# LCMeter_test_power_inverter.net
KiCad netlist of a schematic drawn in EAGLE
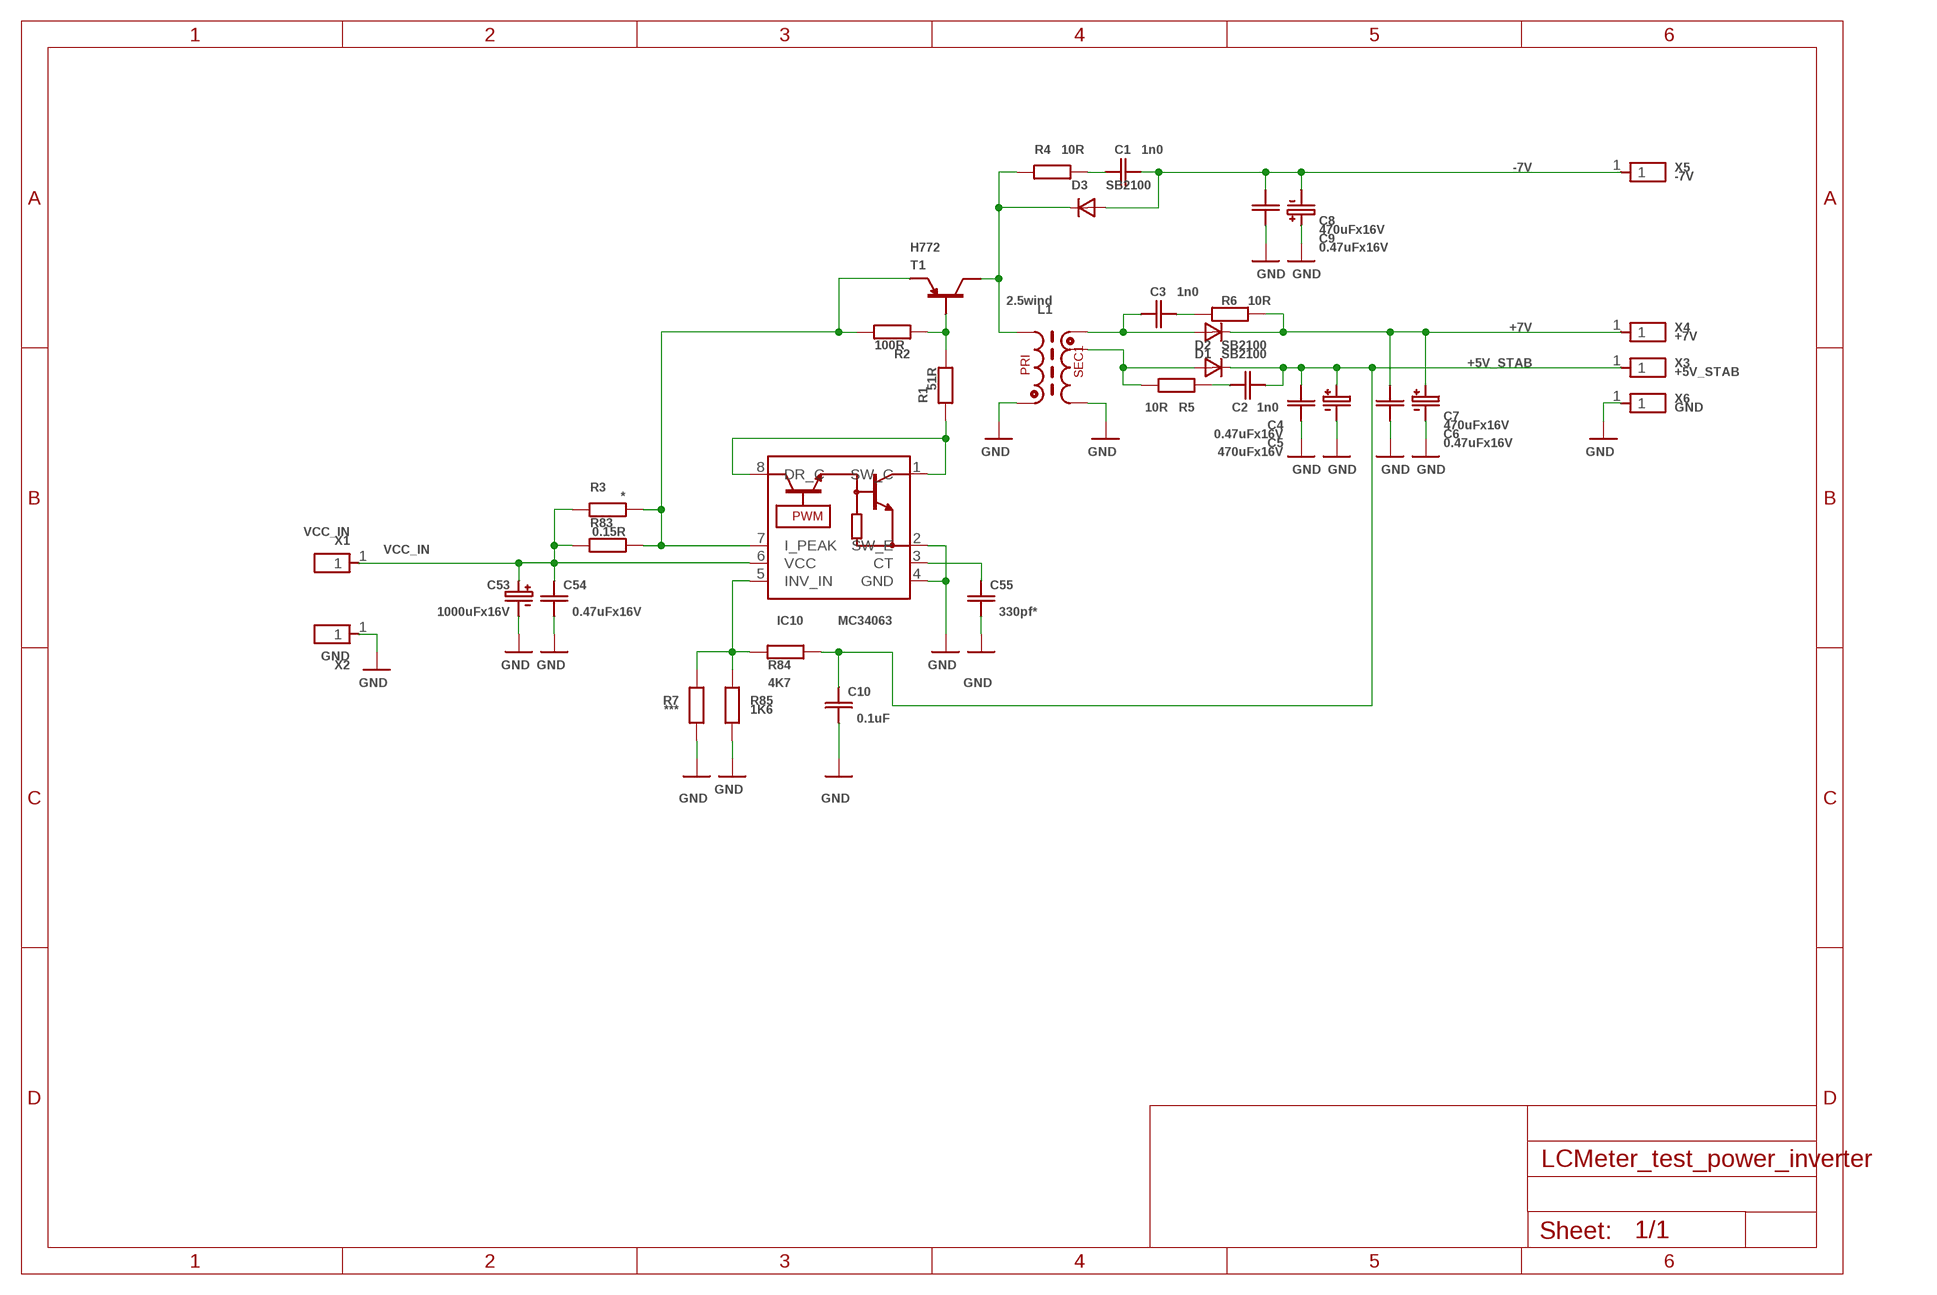
[diagram p0: schematic, sheet 1]

(export (version "E")
  (design (tool "Eeschema 10.0.6"))
  (components
    (comp (ref "C1")
      (value "1n0")
      (footprint "eagle-import:RSMD_0805")
      (libsource (lib "eagle-import") (part "CSMD_0805"))
    )
    (comp (ref "C2")
      (value "1n0")
      (footprint "eagle-import:RSMD_0805")
      (libsource (lib "eagle-import") (part "CSMD_0805"))
    )
    (comp (ref "C3")
      (value "1n0")
      (footprint "eagle-import:RSMD_0805")
      (libsource (lib "eagle-import") (part "CSMD_0805"))
    )
    (comp (ref "C4")
      (value "0.47uFx16V")
      (footprint "eagle-import:RSMD_1206_BIG_GAP")
      (libsource (lib "eagle-import") (part "CSMD_1206_BIG_GAP"))
    )
    (comp (ref "C5")
      (value "470uFx16V")
      (footprint "eagle-import:CE_10MM")
      (libsource (lib "eagle-import") (part "CE10MM"))
    )
    (comp (ref "C6")
      (value "0.47uFx16V")
      (footprint "eagle-import:RSMD_1206_BIG_GAP")
      (libsource (lib "eagle-import") (part "CSMD_1206_BIG_GAP"))
    )
    (comp (ref "C7")
      (value "470uFx16V")
      (footprint "eagle-import:CE_10MM")
      (libsource (lib "eagle-import") (part "CE10MM"))
    )
    (comp (ref "C8")
      (value "470uFx16V")
      (footprint "eagle-import:CE_10MM")
      (libsource (lib "eagle-import") (part "CE10MM"))
    )
    (comp (ref "C9")
      (value "0.47uFx16V")
      (footprint "eagle-import:RSMD_1206_BIG_GAP")
      (libsource (lib "eagle-import") (part "CSMD_1206_BIG_GAP"))
    )
    (comp (ref "C10")
      (value "0.1uF")
      (footprint "eagle-import:RSMD_0805")
      (libsource (lib "eagle-import") (part "CSMD_0805"))
    )
    (comp (ref "C53")
      (value "1000uFx16V")
      (footprint "eagle-import:CE_10MM")
      (libsource (lib "eagle-import") (part "CE10MM"))
    )
    (comp (ref "C54")
      (value "0.47uFx16V")
      (footprint "eagle-import:RSMD_1206")
      (libsource (lib "eagle-import") (part "CSMD_1206"))
    )
    (comp (ref "C55")
      (value "330pf*")
      (footprint "eagle-import:RSMD_0805")
      (libsource (lib "eagle-import") (part "CSMD_0805"))
    )
    (comp (ref "D1")
      (value "SB2100")
      (footprint "eagle-import:DO-41_12.5MM")
      (libsource (lib "eagle-import") (part "1N4001DO-41_12.5MM"))
    )
    (comp (ref "D2")
      (value "SB2100")
      (footprint "eagle-import:DO-41_5MM")
      (libsource (lib "eagle-import") (part "1N4001DO-41_5MM"))
    )
    (comp (ref "D3")
      (value "SB2100")
      (footprint "eagle-import:DO-41_12.5MM")
      (libsource (lib "eagle-import") (part "1N4001DO-41_12.5MM"))
    )
    (comp (ref "IC10")
      (value "MC34063")
      (footprint "eagle-import:SOIC8")
      (libsource (lib "eagle-import") (part "MC34063(SO-8)"))
    )
    (comp (ref "L1")
      (value "2.5wind")
      (footprint "eagle-import:RING_16X8_2.5WIND")
      (libsource (lib "eagle-import") (part "TRANS_2.5_WIND16X8"))
    )
    (comp (ref "R1")
      (value "51R")
      (footprint "eagle-import:RSMD_1206_BIG_GAP")
      (libsource (lib "eagle-import") (part "RSMD_1206_BIG_GAP"))
    )
    (comp (ref "R2")
      (value "100R")
      (footprint "eagle-import:RSMD_0805")
      (libsource (lib "eagle-import") (part "RSMD_0805"))
    )
    (comp (ref "R3")
      (value "*")
      (footprint "eagle-import:RSMD_1206_BIG_GAP")
      (libsource (lib "eagle-import") (part "RSMD_1206_BIG_GAP"))
    )
    (comp (ref "R4")
      (value "10R")
      (footprint "eagle-import:RSMD_1206_BIG_GAP")
      (libsource (lib "eagle-import") (part "RSMD_1206_BIG_GAP"))
    )
    (comp (ref "R5")
      (value "10R")
      (footprint "eagle-import:RSMD_1206_BIG_GAP")
      (libsource (lib "eagle-import") (part "RSMD_1206_BIG_GAP"))
    )
    (comp (ref "R6")
      (value "10R")
      (footprint "eagle-import:RSMD_1206_BIG_GAP")
      (libsource (lib "eagle-import") (part "RSMD_1206_BIG_GAP"))
    )
    (comp (ref "R7")
      (value "***")
      (footprint "eagle-import:RSMD_0805")
      (libsource (lib "eagle-import") (part "RSMD_0805"))
    )
    (comp (ref "R83")
      (value "0.15R")
      (footprint "eagle-import:RSMD_1206_BIG_GAP")
      (libsource (lib "eagle-import") (part "RSMD_1206_BIG_GAP"))
    )
    (comp (ref "R84")
      (value "4K7")
      (footprint "eagle-import:R0207")
      (libsource (lib "eagle-import") (part "R0207"))
    )
    (comp (ref "R85")
      (value "1K6")
      (footprint "eagle-import:RSMD_0805")
      (libsource (lib "eagle-import") (part "RSMD_0805"))
    )
    (comp (ref "T1")
      (value "H772")
      (footprint "eagle-import:DPAK")
      (libsource (lib "eagle-import") (part "H772_PNPDPAK"))
    )
    (comp (ref "X1")
      (value "VCC_IN")
      (footprint "eagle-import:PIN1X1_3.5MM_PWR")
      (libsource (lib "eagle-import") (part "PIN1X13.5MM_PWR"))
    )
    (comp (ref "X2")
      (value "GND")
      (footprint "eagle-import:PIN1X1_3.5MM_PWR")
      (libsource (lib "eagle-import") (part "PIN1X13.5MM_PWR"))
    )
    (comp (ref "X3")
      (value "+5V_STAB")
      (footprint "eagle-import:PIN1X1_3.5MM_PWR")
      (libsource (lib "eagle-import") (part "PIN1X13.5MM_PWR"))
    )
    (comp (ref "X4")
      (value "+7V")
      (footprint "eagle-import:PIN1X1_3.5MM_PWR")
      (libsource (lib "eagle-import") (part "PIN1X13.5MM_PWR"))
    )
    (comp (ref "X5")
      (value "-7V")
      (footprint "eagle-import:PIN1X1_3.5MM_PWR")
      (libsource (lib "eagle-import") (part "PIN1X13.5MM_PWR"))
    )
    (comp (ref "X6")
      (value "GND")
      (footprint "eagle-import:PIN1X1_3.5MM_PWR")
      (libsource (lib "eagle-import") (part "PIN1X13.5MM_PWR"))
    )
  )
  (nets
    (net (code "1") (name "/+5V_STAB") (class "Default")
      (node (ref "C10") (pin "PAD_1") (pinfunction "PIN1_PAD_1") (pintype "bidirectional"))
      (node (ref "C2") (pin "PAD_0") (pinfunction "PIN0_PAD_0") (pintype "bidirectional"))
      (node (ref "C4") (pin "PAD_1") (pinfunction "PIN1_PAD_1") (pintype "bidirectional"))
      (node (ref "C5") (pin "PLUS") (pinfunction "PLUS_PLUS") (pintype "bidirectional"))
      (node (ref "D1") (pin "CATHODE") (pinfunction "CATHODE_CATHODE") (pintype "passive"))
      (node (ref "R84") (pin "PAD1") (pinfunction "PIN1_PAD1") (pintype "passive"))
      (node (ref "X3") (pin "1") (pinfunction "1_1") (pintype "bidirectional"))
    )
    (net (code "2") (name "/+7V") (class "Default")
      (node (ref "C6") (pin "PAD_1") (pinfunction "PIN1_PAD_1") (pintype "bidirectional"))
      (node (ref "C7") (pin "PLUS") (pinfunction "PLUS_PLUS") (pintype "bidirectional"))
      (node (ref "D2") (pin "CATHODE") (pinfunction "CATHODE_CATHODE") (pintype "passive"))
      (node (ref "R6") (pin "PAD_0") (pinfunction "PIN0_PAD_0") (pintype "passive"))
      (node (ref "X4") (pin "1") (pinfunction "1_1") (pintype "bidirectional"))
    )
    (net (code "3") (name "/-7V") (class "Default")
      (node (ref "C1") (pin "PAD_0") (pinfunction "PIN0_PAD_0") (pintype "bidirectional"))
      (node (ref "C8") (pin "MINUS") (pinfunction "MINUS_MINUS") (pintype "bidirectional"))
      (node (ref "C9") (pin "PAD_1") (pinfunction "PIN1_PAD_1") (pintype "bidirectional"))
      (node (ref "D3") (pin "ANODE") (pinfunction "ANODE_ANODE") (pintype "passive"))
      (node (ref "X5") (pin "1") (pinfunction "1_1") (pintype "bidirectional"))
    )
    (net (code "4") (name "/VCC_IN") (class "Default")
      (node (ref "C53") (pin "PLUS") (pinfunction "PLUS_PLUS") (pintype "bidirectional"))
      (node (ref "C54") (pin "PAD_1") (pinfunction "PIN1_PAD_1") (pintype "bidirectional"))
      (node (ref "IC10") (pin "6") (pinfunction "VCC_6") (pintype "bidirectional"))
      (node (ref "R3") (pin "PAD_0") (pinfunction "PIN0_PAD_0") (pintype "passive"))
      (node (ref "R83") (pin "PAD_0") (pinfunction "PIN0_PAD_0") (pintype "passive"))
      (node (ref "X1") (pin "1") (pinfunction "1_1") (pintype "bidirectional"))
    )
    (net (code "5") (name "GND") (class "Default")
      (node (ref "C10") (pin "PAD_0") (pinfunction "PIN0_PAD_0") (pintype "bidirectional"))
      (node (ref "C4") (pin "PAD_0") (pinfunction "PIN0_PAD_0") (pintype "bidirectional"))
      (node (ref "C5") (pin "MINUS") (pinfunction "MINUS_MINUS") (pintype "bidirectional"))
      (node (ref "C53") (pin "MINUS") (pinfunction "MINUS_MINUS") (pintype "bidirectional"))
      (node (ref "C54") (pin "PAD_0") (pinfunction "PIN0_PAD_0") (pintype "bidirectional"))
      (node (ref "C55") (pin "PAD_0") (pinfunction "PIN0_PAD_0") (pintype "bidirectional"))
      (node (ref "C6") (pin "PAD_0") (pinfunction "PIN0_PAD_0") (pintype "bidirectional"))
      (node (ref "C7") (pin "MINUS") (pinfunction "MINUS_MINUS") (pintype "bidirectional"))
      (node (ref "C8") (pin "PLUS") (pinfunction "PLUS_PLUS") (pintype "bidirectional"))
      (node (ref "C9") (pin "PAD_0") (pinfunction "PIN0_PAD_0") (pintype "bidirectional"))
      (node (ref "IC10") (pin "2") (pinfunction "SW_E_2") (pintype "bidirectional"))
      (node (ref "IC10") (pin "4") (pinfunction "GND_4") (pintype "bidirectional"))
      (node (ref "L1") (pin "W1_START") (pinfunction "PRI_START_W1_START") (pintype "bidirectional"))
      (node (ref "L1") (pin "W2_END") (pinfunction "SEC1_END_W2_END") (pintype "bidirectional"))
      (node (ref "R7") (pin "PAD_0") (pinfunction "PIN0_PAD_0") (pintype "passive"))
      (node (ref "R85") (pin "PAD_0") (pinfunction "PIN0_PAD_0") (pintype "passive"))
      (node (ref "X2") (pin "1") (pinfunction "1_1") (pintype "bidirectional"))
      (node (ref "X6") (pin "1") (pinfunction "1_1") (pintype "bidirectional"))
    )
    (net (code "6") (name "Net-(C1-PIN1)") (class "Default")
      (node (ref "C1") (pin "PAD_1") (pinfunction "PIN1_PAD_1") (pintype "bidirectional"))
      (node (ref "R4") (pin "PAD_0") (pinfunction "PIN0_PAD_0") (pintype "passive"))
    )
    (net (code "7") (name "Net-(C2-PIN1)") (class "Default")
      (node (ref "C2") (pin "PAD_1") (pinfunction "PIN1_PAD_1") (pintype "bidirectional"))
      (node (ref "R5") (pin "PAD_1") (pinfunction "PIN1_PAD_1") (pintype "passive"))
    )
    (net (code "8") (name "Net-(C3-PIN0)") (class "Default")
      (node (ref "C3") (pin "PAD_0") (pinfunction "PIN0_PAD_0") (pintype "bidirectional"))
      (node (ref "R6") (pin "PAD_1") (pinfunction "PIN1_PAD_1") (pintype "passive"))
    )
    (net (code "9") (name "Net-(C3-PIN1)") (class "Default")
      (node (ref "C3") (pin "PAD_1") (pinfunction "PIN1_PAD_1") (pintype "bidirectional"))
      (node (ref "D2") (pin "ANODE") (pinfunction "ANODE_ANODE") (pintype "passive"))
      (node (ref "L1") (pin "W2_START") (pinfunction "SEC1_START_W2_START") (pintype "bidirectional"))
    )
    (net (code "10") (name "Net-(C55-PIN1)") (class "Default")
      (node (ref "C55") (pin "PAD_1") (pinfunction "PIN1_PAD_1") (pintype "bidirectional"))
      (node (ref "IC10") (pin "3") (pinfunction "CT_3") (pintype "bidirectional"))
    )
    (net (code "11") (name "Net-(IC10-DR_C)") (class "Default")
      (node (ref "IC10") (pin "1") (pinfunction "SW_C_1") (pintype "bidirectional"))
      (node (ref "IC10") (pin "8") (pinfunction "DR_C_8") (pintype "bidirectional"))
      (node (ref "R1") (pin "PAD_0") (pinfunction "PIN0_PAD_0") (pintype "passive"))
    )
    (net (code "12") (name "Net-(IC10-INV_IN)") (class "Default")
      (node (ref "IC10") (pin "5") (pinfunction "INV_IN_5") (pintype "bidirectional"))
      (node (ref "R7") (pin "PAD_1") (pinfunction "PIN1_PAD_1") (pintype "passive"))
      (node (ref "R84") (pin "PAD_0") (pinfunction "PIN0_PAD_0") (pintype "passive"))
      (node (ref "R85") (pin "PAD_1") (pinfunction "PIN1_PAD_1") (pintype "passive"))
    )
    (net (code "13") (name "Net-(IC10-I_PEAK)") (class "Default")
      (node (ref "IC10") (pin "7") (pinfunction "I_PEAK_7") (pintype "bidirectional"))
      (node (ref "R2") (pin "PAD_1") (pinfunction "PIN1_PAD_1") (pintype "passive"))
      (node (ref "R3") (pin "PAD_1") (pinfunction "PIN1_PAD_1") (pintype "passive"))
      (node (ref "R83") (pin "PAD_1") (pinfunction "PIN1_PAD_1") (pintype "passive"))
      (node (ref "T1") (pin "3") (pinfunction "E_3") (pintype "bidirectional"))
    )
    (net (code "14") (name "Net-(L1-PRI_END)") (class "Default")
      (node (ref "D3") (pin "CATHODE") (pinfunction "CATHODE_CATHODE") (pintype "passive"))
      (node (ref "L1") (pin "W1_END") (pinfunction "PRI_END_W1_END") (pintype "bidirectional"))
      (node (ref "R4") (pin "PAD_1") (pinfunction "PIN1_PAD_1") (pintype "passive"))
      (node (ref "T1") (pin "2") (pinfunction "C_2") (pintype "bidirectional"))
    )
    (net (code "15") (name "Net-(L1-SEC1_NEAR_START)") (class "Default")
      (node (ref "D1") (pin "ANODE") (pinfunction "ANODE_ANODE") (pintype "passive"))
      (node (ref "L1") (pin "W2_NEAR_START") (pinfunction "SEC1_NEAR_START_W2_NEAR_START") (pintype "bidirectional"))
      (node (ref "R5") (pin "PAD_0") (pinfunction "PIN0_PAD_0") (pintype "passive"))
    )
    (net (code "16") (name "Net-(R1-PIN1)") (class "Default")
      (node (ref "R1") (pin "PAD_1") (pinfunction "PIN1_PAD_1") (pintype "passive"))
      (node (ref "R2") (pin "PAD_0") (pinfunction "PIN0_PAD_0") (pintype "passive"))
      (node (ref "T1") (pin "1") (pinfunction "B_1") (pintype "bidirectional"))
    )
  )
)
